# PowerStage.net
KiCad netlist of a schematic drawn in Altium Designer
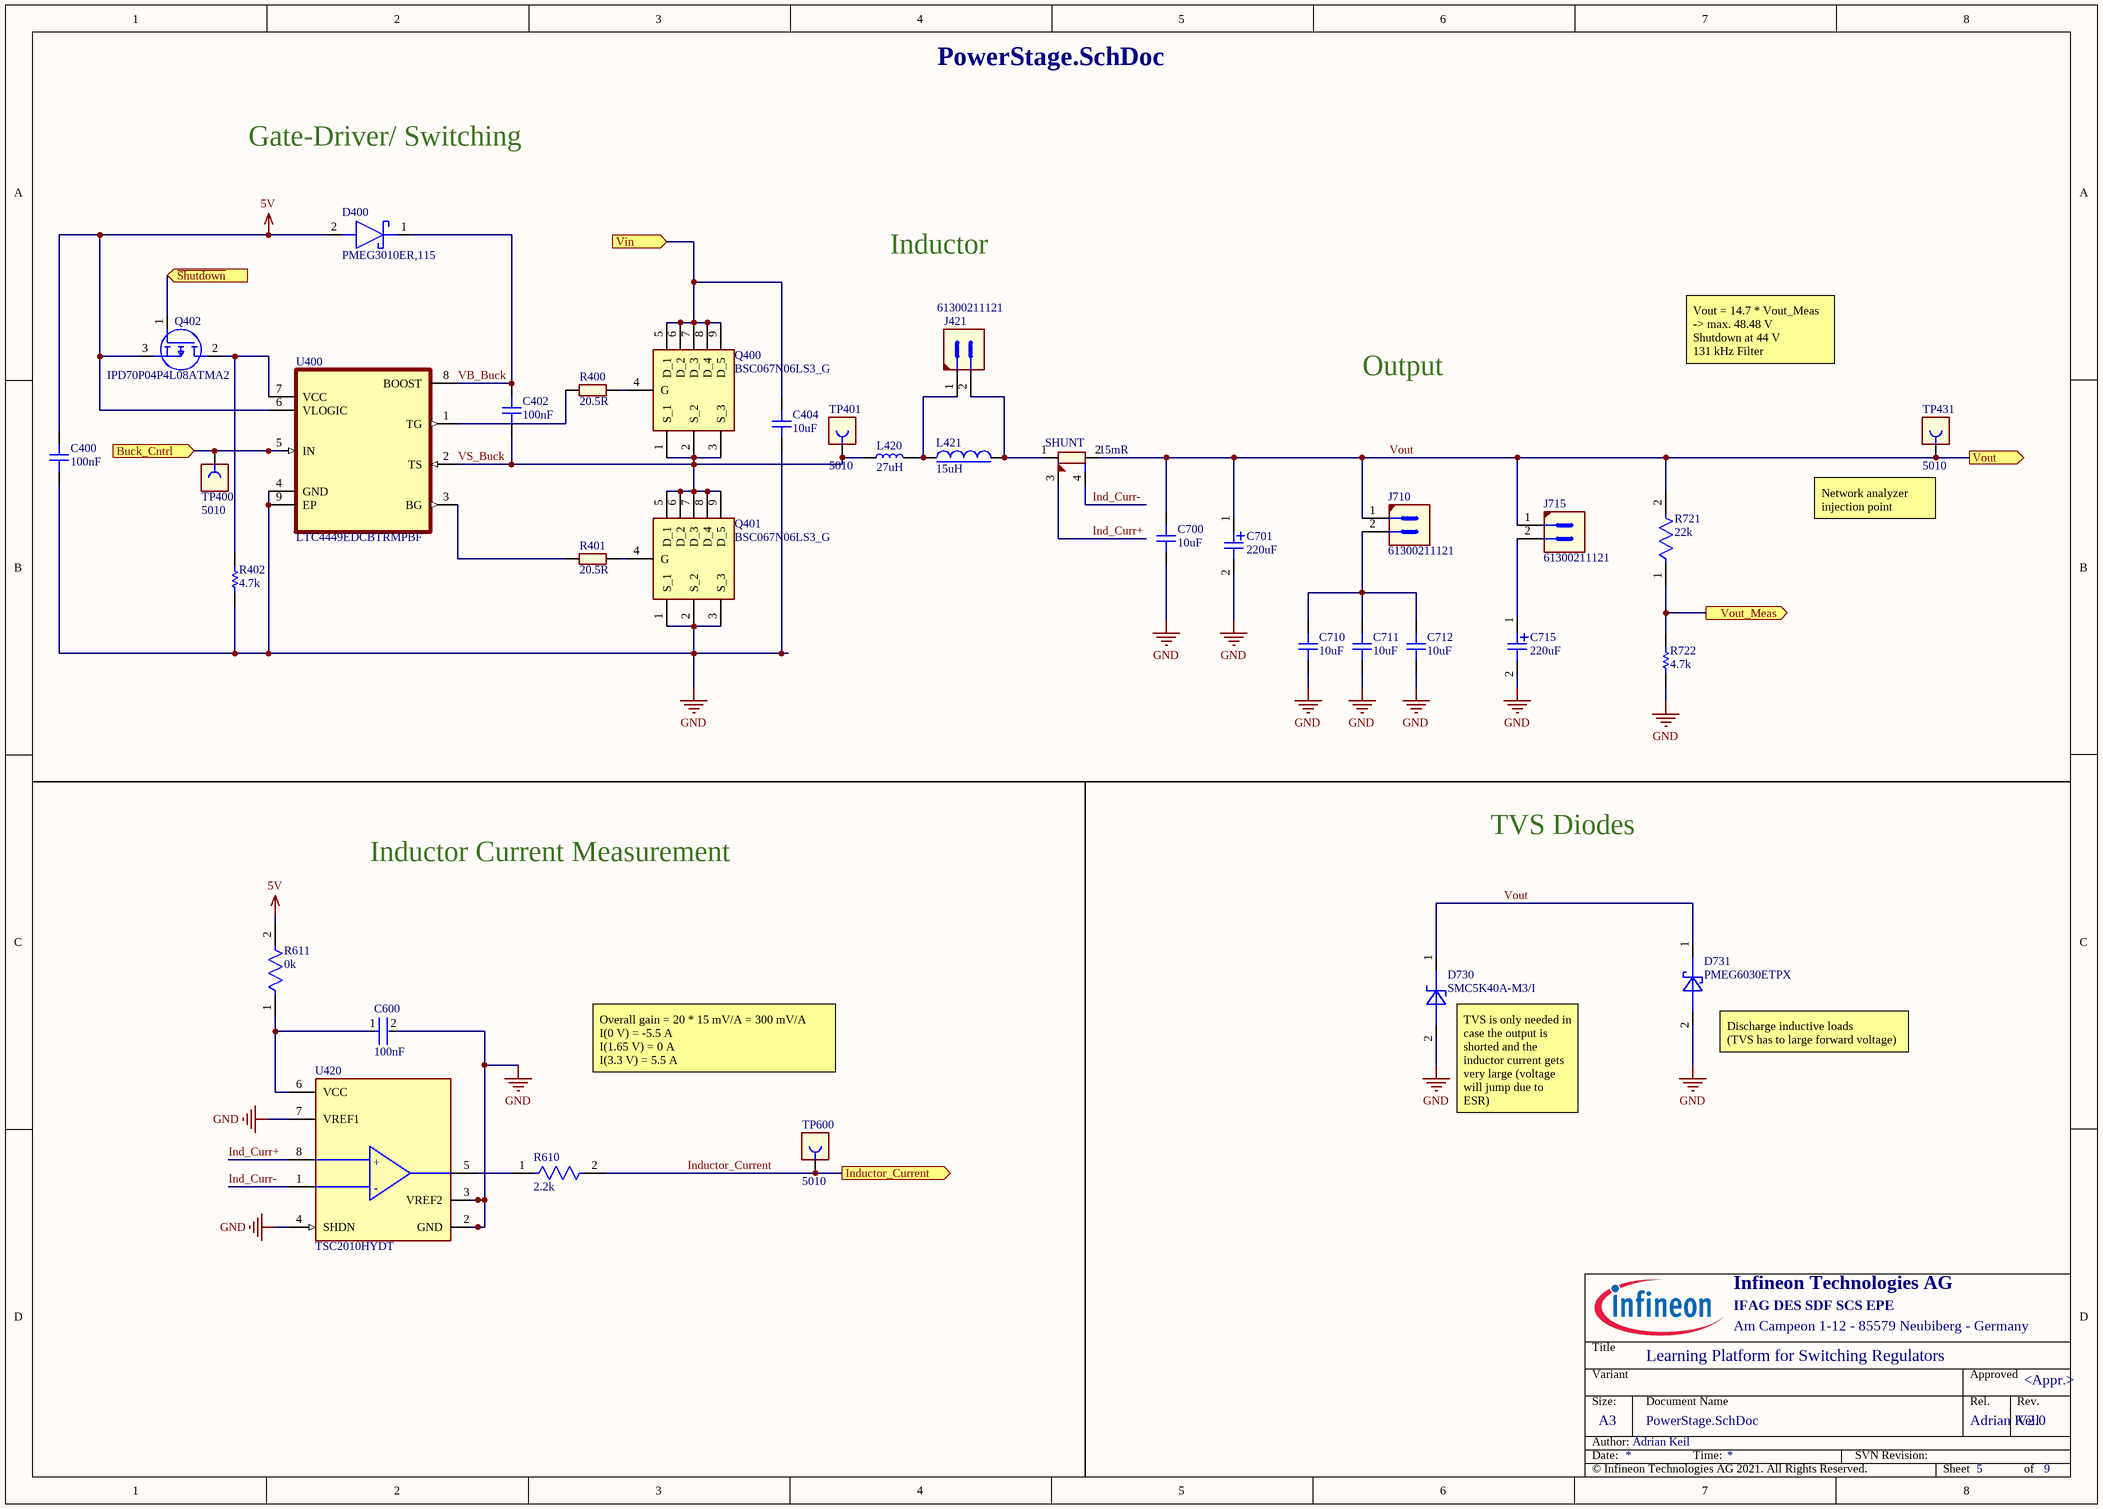
[diagram p0: PowerStage.SchDoc]

(export (version "E")
  (design (tool "Eeschema 10.0.6"))
  (components
    (comp (ref "C400")
      (value "100nF")
      (footprint "CAPC3216X125N-0")
      (description "CAP / CERA / 100nF / 50V / 10% / X7R (EIA) / -55°C to 125°C / 1206(3216) / SMD / -")
      (fields (field (name "LEGACY PARTNUMBER") "CAP01005660") (field (name "MANUFACTURER") "MuRata"))
      (libsource (lib "PCBLibraryData") (part "CAP-SGL-STD-02P_00000001"))
    )
    (comp (ref "C402")
      (value "100nF")
      (footprint "CAPC3216X125N-0")
      (description "CAP / CERA / 100nF / 50V / 10% / X7R (EIA) / -55°C to 125°C / 1206(3216) / SMD / -")
      (fields (field (name "LEGACY PARTNUMBER") "CAP01005660") (field (name "MANUFACTURER") "MuRata"))
      (libsource (lib "PCBLibraryData") (part "CAP-SGL-STD-02P_00000001"))
    )
    (comp (ref "C404")
      (value "10uF")
      (footprint "CAPC3216X190N-1")
      (description "CAP / CERA / 10uF / 50V / 20% / X5R (EIA) / -55°C to 85°C / 1206 (3216) / SMD / -")
      (fields (field (name "MANUFACTURER") "Taiyo Yuden"))
      (libsource (lib "PCBLibraryData") (part "CAP-SGL-STD-02P_00000001"))
    )
    (comp (ref "C600")
      (value "100nF")
      (footprint "FP-1206-L_3_2_0_2-W_1_6_0-MFG")
      (description "General Purpose Ceramic Capacitor, 1206, 100nF, 10%, X7R, 15%, 100V")
      (fields (field (name "TOLERANCE") "10%"))
      (libsource (lib "Altium Content Vault") (part "b4654b650e69147ec39a6b967a45e02"))
    )
    (comp (ref "C700")
      (value "10uF")
      (footprint "CAPC3216X190N-1")
      (description "CAP / CERA / 10uF / 50V / 20% / X5R (EIA) / -55°C to 85°C / 1206 (3216) / SMD / -")
      (fields (field (name "MANUFACTURER") "Taiyo Yuden"))
      (libsource (lib "PCBLibraryData") (part "CAP-SGL-STD-02P_00000001"))
    )
    (comp (ref "C701")
      (value "220uF")
      (footprint "CAPAE1030X1050N-3")
      (fields (field (name "MANUFACTURER") "Nippon Chemi-Con"))
      (libsource (lib "PCBLibraryData") (part "CAP-SGL-POL-02P_00000002"))
    )
    (comp (ref "C710")
      (value "10uF")
      (footprint "CAPC3216X190N-1")
      (description "CAP / CERA / 10uF / 50V / 20% / X5R (EIA) / -55°C to 85°C / 1206 (3216) / SMD / -")
      (fields (field (name "MANUFACTURER") "Taiyo Yuden") (field (name "LCSC PART #") "C97712"))
      (libsource (lib "PCBLibraryData") (part "CAP-SGL-STD-02P_00000001"))
    )
    (comp (ref "C711")
      (value "10uF")
      (footprint "CAPC3216X190N-1")
      (description "CAP / CERA / 10uF / 50V / 20% / X5R (EIA) / -55°C to 85°C / 1206 (3216) / SMD / -")
      (fields (field (name "MANUFACTURER") "Taiyo Yuden"))
      (libsource (lib "PCBLibraryData") (part "CAP-SGL-STD-02P_00000001"))
    )
    (comp (ref "C712")
      (value "10uF")
      (footprint "CAPC3216X190N-1")
      (description "CAP / CERA / 10uF / 50V / 20% / X5R (EIA) / -55°C to 85°C / 1206 (3216) / SMD / -")
      (fields (field (name "MANUFACTURER") "Taiyo Yuden"))
      (libsource (lib "PCBLibraryData") (part "CAP-SGL-STD-02P_00000001"))
    )
    (comp (ref "C715")
      (value "220uF")
      (footprint "CAPAE1030X1050N-3")
      (fields (field (name "MANUFACTURER") "Nippon Chemi-Con"))
      (libsource (lib "PCBLibraryData") (part "CAP-SGL-POL-02P_00000002"))
    )
    (comp (ref "D400")
      (value "PMEG3010ER,115")
      (footprint "myPcbLib:PMEG3010ER115")
      (description "Schottky Diode")
      (fields (field (name "MOUSER PART NUMBER") "771-PMEG3010ER115"))
      (libsource (lib "mySchlib") (part "PMEG3010ER,115"))
    )
    (comp (ref "D730")
      (value "SMC5K40A-M3/I")
      (footprint "DIOM7959X262N")
      (description "Surface Mount Transient Voltage Suppressors, Unidirectional, Very Fast Response Time")
      (fields (field (name "MANUFACTURER") "Vishay") (field (name "MPN") "5.0SMDJ40AS"))
      (libsource (lib "PCBLibraryData") (part "d_tvs_a"))
    )
    (comp (ref "D731")
      (value "PMEG6030ETPX")
      (footprint "SODFL4725X110N")
      (description "DIODE SCHOTTKY 60V 3A SOD128")
      (fields (field (name "MANUFACTURER") "Nexperia"))
      (libsource (lib "PCBLibraryData") (part "d_schottky_a"))
    )
    (comp (ref "J421")
      (value "61300211121")
      (footprint "CON-M-THT-61300211121")
      (description "Header, 2.54mm Pitch, 2 pin, Vertical, Single Row")
      (fields
        (field (name "LEGACY PARTNUMBER") "CON01500943")
        (field (name "MANUFACTURER") "Wurth Elektronik")
      )
      (libsource (lib "") (part "Header 2_1"))
    )
    (comp (ref "J710")
      (value "61300211121")
      (footprint "CON-M-THT-61300211121")
      (description "Header, 2.54mm Pitch, 2 pin, Vertical, Single Row")
      (fields
        (field (name "LEGACY PARTNUMBER") "CON01500943")
        (field (name "MANUFACTURER") "Wurth Elektronik")
      )
      (libsource (lib "PCBLibraryData") (part "Header 2"))
    )
    (comp (ref "J715")
      (value "61300211121")
      (footprint "CON-M-THT-61300211121")
      (description "Header, 2.54mm Pitch, 2 pin, Vertical, Single Row")
      (fields
        (field (name "LEGACY PARTNUMBER") "CON01500943")
        (field (name "MANUFACTURER") "Wurth Elektronik")
      )
      (libsource (lib "PCBLibraryData") (part "Header 2"))
    )
    (comp (ref "L420")
      (value "27uH")
      (footprint "INDM120120X1000N")
      (fields
        (field (name "MANUFACTURER") "Wurth Elektronik")
        (field (name "LCSC PART #") "C6404671")
        (field (name "MPN") "7447709270")
      )
      (libsource (lib "PCBLibraryData") (part "IND-SGL-STD-02P_00000015"))
    )
    (comp (ref "L421")
      (value "15uH")
      (footprint "IND-SMD-SRP6060FA")
      (fields
        (field (name "MANUFACTURER") "Bourns")
        (field (name "LCSC PART #") "C2047415")
        (field (name "MPN") "SRP6060FA-150M")
      )
      (libsource (lib "PCBLibraryData") (part "IND-SGL-STD-COR-02P_00000016"))
    )
    (comp (ref "Q400")
      (value "BSC067N06LS3_G")
      (footprint "myPcbLib:BSC080N03LSG")
      (description "MOSFET (N-Channel)")
      (fields
        (field (name "MANUFACTURER_PART_NUMBER") "BSC067N06LS3 G")
        (field (name "MOUSER PART NUMBER") "726-BSC067N06LS3G")
      )
      (libsource (lib "mySchlib") (part "BSC067N06LS3_G"))
    )
    (comp (ref "Q401")
      (value "BSC067N06LS3_G")
      (footprint "myPcbLib:BSC080N03LSG")
      (description "MOSFET (N-Channel)")
      (fields
        (field (name "MANUFACTURER_PART_NUMBER") "BSC067N06LS3 G")
        (field (name "MOUSER PART NUMBER") "726-BSC067N06LS3G")
      )
      (libsource (lib "mySchlib") (part "BSC067N06LS3_G"))
    )
    (comp (ref "Q402")
      (value "IPD70P04P4L08ATMA2")
      (footprint "myPcbLib:IPD70P04P4L08ATMA2")
      (description "MOSFET (P-Channel)")
      (fields (field (name "MOUSER PART NUMBER") "726-IPD70P04P4L08ATM"))
      (libsource (lib "mySchlib") (part "IPD70P04P4L08ATMA2"))
    )
    (comp (ref "R400")
      (value "20.5R")
      (footprint "RESC3216X60N")
      (description "RES / STD / 20.5R / 250mW / 1% / 100ppm/K / -55°C to 155°C / 1206(3216) / SMD / -")
      (fields (field (name "LEGACY PARTNUMBER") "RES01802548") (field (name "MANUFACTURER") "Vishay"))
      (libsource (lib "PCBLibraryData") (part "RES-SGL-STD-02P_00000006"))
    )
    (comp (ref "R401")
      (value "20.5R")
      (footprint "RESC3216X60N")
      (description "RES / STD / 20.5R / 250mW / 1% / 100ppm/K / -55°C to 155°C / 1206(3216) / SMD / -")
      (fields (field (name "LEGACY PARTNUMBER") "RES01802548") (field (name "MANUFACTURER") "Vishay"))
      (libsource (lib "PCBLibraryData") (part "RES-SGL-STD-02P_00000006"))
    )
    (comp (ref "R402")
      (value "4.7k")
      (footprint "RESC3216X60X45ML15T20")
      (description "Chip Resistor, 4.7 KOhm, +/- 1%, 0.25 W, -55 to 155 degC, 1206 (3216 Metric), RoHS, Tape and Reel")
      (fields (field (name "MANUFACTURER") "Vishay Semiconductor") (field (name "TOLERANCE") "1%"))
      (libsource (lib "Altium Content Vault") (part "RES-2"))
    )
    (comp (ref "R610")
      (value "2.2k")
      (footprint "FP-CRCW1206-e3-IPC_C")
      (description "RES Thick Film, 2.2kΩ, 1%, 0.25W, 100ppm/°C, 1206")
      (fields (field (name "TOLERANCE") "1%"))
      (libsource (lib "Altium Content Vault") (part "1029c3af85768c4190bb7ad29bc67b5"))
    )
    (comp (ref "R611")
      (value "0k")
      (footprint "FP-CRCW1206-e3-IPC_C")
      (description "RES Thick Film, 0Ω, 0.25W, 1206")
      (fields (field (name "TOLERANCE") "1%") (field (name "LCSC PART #") "C844861"))
      (libsource (lib "Altium Content Vault") (part "1029c3af85768c4190bb7ad29bc67b5"))
    )
    (comp (ref "R721")
      (value "22k")
      (footprint "FP-CRCW1206-e3-IPC_A")
      (description "RES Thick Film, 22kΩ, 1%, 0.25W, 100ppm/°C, 1206")
      (fields (field (name "TOLERANCE") "1%"))
      (libsource (lib "Altium Content Vault") (part "1029c3af85768c4190bb7ad29bc67b5"))
    )
    (comp (ref "R722")
      (value "4.7k")
      (footprint "RESC3216X60X45ML15T20")
      (description "Chip Resistor, 4.7 KOhm, +/- 1%, 0.25 W, -55 to 155 degC, 1206 (3216 Metric), RoHS, Tape and Reel")
      (fields (field (name "MANUFACTURER") "Vishay Semiconductor") (field (name "TOLERANCE") "1%"))
      (libsource (lib "Altium Content Vault") (part "RES-2"))
    )
    (comp (ref "SHUNT")
      (value "15mR")
      (footprint "RES-SMD-L4T12")
      (description "RES / STD / 15mR / 500mW / 1% / 75ppm/K / -55°C to 155°C / 1206 (3216) / SMD / -")
      (fields (field (name "MANUFACTURER") "Ohmite"))
      (libsource (lib "PCBLibraryData") (part "RES-SHT-STD-04P_00097BE5"))
    )
    (comp (ref "TP400")
      (value "5010")
      (footprint "CON-THT-TP-5010")
      (description "PC Test Point-Multipurpose THT, Red")
      (fields
        (field (name "LEGACY PARTNUMBER") "CON01500529")
        (field (name "MANUFACTURER") "Keystone Electronics Corp.")
      )
      (libsource (lib "") (part "connector_1_f_1"))
    )
    (comp (ref "TP401")
      (value "5010")
      (footprint "CON-THT-TP-5010")
      (description "PC Test Point-Multipurpose THT, Red")
      (fields
        (field (name "LEGACY PARTNUMBER") "CON01500529")
        (field (name "MANUFACTURER") "Keystone Electronics Corp.")
      )
      (libsource (lib "PCBLibraryData") (part "connector_1_f"))
    )
    (comp (ref "TP431")
      (value "5010")
      (footprint "CON-THT-TP-5010")
      (description "PC Test Point-Multipurpose THT, Red")
      (fields
        (field (name "LEGACY PARTNUMBER") "CON01500529")
        (field (name "MANUFACTURER") "Keystone Electronics Corp.")
      )
      (libsource (lib "PCBLibraryData") (part "connector_1_f"))
    )
    (comp (ref "TP600")
      (value "5010")
      (footprint "CON-THT-TP-5010")
      (description "PC Test Point-Multipurpose THT, Red")
      (fields
        (field (name "LEGACY PARTNUMBER") "CON01500529")
        (field (name "MANUFACTURER") "Keystone Electronics Corp.")
      )
      (libsource (lib "PCBLibraryData") (part "connector_1_f"))
    )
    (comp (ref "U400")
      (value "LTC4449EDCBTRMPBF")
      (footprint "DFN200X300X80-9N")
      (description "High Speed Synchronous N-Channel MOSFET Driver")
      (fields (field (name "LCSC PART #") "C580913") (field (name "MPN") "LTC4449EDCB#TRMPBF"))
      (libsource (lib "mySchlib") (part "LTC4449EDCBTRMPBF"))
    )
    (comp (ref "U420")
      (value "TSC2010HYDT")
      (footprint "FP-SO8-IPC_C")
      (description "IC CURRENT SENSE 1 CIRCUIT 8SOIC")
      (fields (field (name "LCSC PART #") "C4370994"))
      (libsource (lib "Altium Content Vault") (part "148e0707e4e6d103058ae51fa0bcede"))
    )
  )
  (nets
    (net (code "1") (name "/Buck_Cntrl") (class "Default")
      (node (ref "TP400") (pin "1") (pinfunction "1_1") (pintype "passive"))
      (node (ref "U400") (pin "5") (pinfunction "IN_5") (pintype "input"))
    )
    (net (code "2") (name "/Ind_Curr+") (class "Default")
      (node (ref "SHUNT") (pin "3") (pinfunction "I1_3") (pintype "passive"))
      (node (ref "U420") (pin "8") (pinfunction "IN+_8") (pintype "tri_state"))
    )
    (net (code "3") (name "/Ind_Curr-") (class "Default")
      (node (ref "SHUNT") (pin "4") (pinfunction "I2_4") (pintype "passive"))
      (node (ref "U420") (pin "1") (pinfunction "IN-_1") (pintype "tri_state"))
    )
    (net (code "4") (name "/Inductor_Current") (class "Default")
      (node (ref "R610") (pin "2") (pinfunction "2_2") (pintype "passive"))
      (node (ref "TP600") (pin "1") (pinfunction "1_1") (pintype "passive"))
    )
    (net (code "5") (name "/Shutdown") (class "Default")
      (node (ref "Q402") (pin "1") (pinfunction "G_1") (pintype "passive"))
    )
    (net (code "6") (name "/VB_Buck") (class "Default")
      (node (ref "C402") (pin "2") (pinfunction "2_2") (pintype "passive"))
      (node (ref "D400") (pin "1") (pinfunction "K_1") (pintype "passive"))
      (node (ref "U400") (pin "8") (pinfunction "BOOST_8") (pintype "power_in"))
    )
    (net (code "7") (name "/VS_Buck") (class "Default")
      (node (ref "C402") (pin "1") (pinfunction "1_1") (pintype "passive"))
      (node (ref "L420") (pin "1") (pinfunction "1_1") (pintype "passive"))
      (node (ref "Q400") (pin "1") (pinfunction "S_1_1") (pintype "passive"))
      (node (ref "Q400") (pin "2") (pinfunction "S_2_2") (pintype "passive"))
      (node (ref "Q400") (pin "3") (pinfunction "S_3_3") (pintype "passive"))
      (node (ref "Q401") (pin "5") (pinfunction "D_1_5") (pintype "passive"))
      (node (ref "Q401") (pin "6") (pinfunction "D_2_6") (pintype "passive"))
      (node (ref "Q401") (pin "7") (pinfunction "D_3_7") (pintype "passive"))
      (node (ref "Q401") (pin "8") (pinfunction "D_4_8") (pintype "passive"))
      (node (ref "Q401") (pin "9") (pinfunction "D_5_9") (pintype "passive"))
      (node (ref "TP401") (pin "1") (pinfunction "1_1") (pintype "passive"))
      (node (ref "U400") (pin "2") (pinfunction "TS_2") (pintype "input"))
    )
    (net (code "8") (name "/Vin") (class "Default")
      (node (ref "C404") (pin "2") (pinfunction "2_2") (pintype "passive"))
      (node (ref "Q400") (pin "5") (pinfunction "D_1_5") (pintype "passive"))
      (node (ref "Q400") (pin "6") (pinfunction "D_2_6") (pintype "passive"))
      (node (ref "Q400") (pin "7") (pinfunction "D_3_7") (pintype "passive"))
      (node (ref "Q400") (pin "8") (pinfunction "D_4_8") (pintype "passive"))
      (node (ref "Q400") (pin "9") (pinfunction "D_5_9") (pintype "passive"))
    )
    (net (code "9") (name "/Vout") (class "Default")
      (node (ref "C700") (pin "2") (pinfunction "2_2") (pintype "passive"))
      (node (ref "C701") (pin "1") (pinfunction "1_1") (pintype "passive"))
      (node (ref "D730") (pin "1") (pinfunction "CATHODE_1") (pintype "passive"))
      (node (ref "D731") (pin "1") (pinfunction "Cathode_1") (pintype "passive"))
      (node (ref "J710") (pin "1") (pinfunction "1_1") (pintype "passive"))
      (node (ref "J715") (pin "1") (pinfunction "1_1") (pintype "passive"))
      (node (ref "R721") (pin "2") (pinfunction "2_2") (pintype "passive"))
      (node (ref "SHUNT") (pin "2") (pinfunction "V2_2") (pintype "passive"))
      (node (ref "TP431") (pin "1") (pinfunction "1_1") (pintype "passive"))
    )
    (net (code "10") (name "/Vout_Meas") (class "Default")
      (node (ref "R721") (pin "1") (pinfunction "1_1") (pintype "passive"))
      (node (ref "R722") (pin "2") (pinfunction "2_2") (pintype "passive"))
    )
    (net (code "11") (name "5V") (class "Default")
      (node (ref "C400") (pin "2") (pinfunction "2_2") (pintype "passive"))
      (node (ref "D400") (pin "2") (pinfunction "A_2") (pintype "passive"))
      (node (ref "Q402") (pin "3") (pinfunction "S_3") (pintype "passive"))
      (node (ref "R611") (pin "2") (pinfunction "2_2") (pintype "passive"))
      (node (ref "U400") (pin "6") (pinfunction "VLOGIC_6") (pintype "power_in"))
    )
    (net (code "12") (name "GND") (class "Default")
      (node (ref "C400") (pin "1") (pinfunction "1_1") (pintype "passive"))
      (node (ref "C404") (pin "1") (pinfunction "1_1") (pintype "passive"))
      (node (ref "C600") (pin "2") (pinfunction "2_2") (pintype "passive"))
      (node (ref "C700") (pin "1") (pinfunction "1_1") (pintype "passive"))
      (node (ref "C701") (pin "2") (pinfunction "2_2") (pintype "passive"))
      (node (ref "C710") (pin "1") (pinfunction "1_1") (pintype "passive"))
      (node (ref "C711") (pin "1") (pinfunction "1_1") (pintype "passive"))
      (node (ref "C712") (pin "1") (pinfunction "1_1") (pintype "passive"))
      (node (ref "C715") (pin "2") (pinfunction "2_2") (pintype "passive"))
      (node (ref "D730") (pin "2") (pinfunction "ANODE_2") (pintype "passive"))
      (node (ref "D731") (pin "2") (pinfunction "Anode_2") (pintype "passive"))
      (node (ref "Q401") (pin "1") (pinfunction "S_1_1") (pintype "passive"))
      (node (ref "Q401") (pin "2") (pinfunction "S_2_2") (pintype "passive"))
      (node (ref "Q401") (pin "3") (pinfunction "S_3_3") (pintype "passive"))
      (node (ref "R402") (pin "1") (pinfunction "1_1") (pintype "passive"))
      (node (ref "R722") (pin "1") (pinfunction "1_1") (pintype "passive"))
      (node (ref "U400") (pin "4") (pinfunction "GND_4") (pintype "passive"))
      (node (ref "U400") (pin "9") (pinfunction "EP_9") (pintype "passive"))
      (node (ref "U420") (pin "2") (pinfunction "GND_2") (pintype "power_in"))
      (node (ref "U420") (pin "3") (pinfunction "VREF2_3") (pintype "passive"))
      (node (ref "U420") (pin "4") (pinfunction "SHDN_4") (pintype "input"))
      (node (ref "U420") (pin "7") (pinfunction "VREF1_7") (pintype "passive"))
    )
    (net (code "13") (name "Net-(C710-Pad2)") (class "Default")
      (node (ref "C710") (pin "2") (pinfunction "2_2") (pintype "passive"))
      (node (ref "C711") (pin "2") (pinfunction "2_2") (pintype "passive"))
      (node (ref "C712") (pin "2") (pinfunction "2_2") (pintype "passive"))
      (node (ref "J710") (pin "2") (pinfunction "2_2") (pintype "passive"))
    )
    (net (code "14") (name "Net-(C715-Pad1)") (class "Default")
      (node (ref "C715") (pin "1") (pinfunction "1_1") (pintype "passive"))
      (node (ref "J715") (pin "2") (pinfunction "2_2") (pintype "passive"))
    )
    (net (code "15") (name "Net-(J421-Pad1)") (class "Default")
      (node (ref "J421") (pin "1") (pinfunction "1_1") (pintype "passive"))
      (node (ref "L420") (pin "2") (pinfunction "2_2") (pintype "passive"))
      (node (ref "L421") (pin "1") (pinfunction "1_1") (pintype "passive"))
    )
    (net (code "16") (name "Net-(Q400-G)") (class "Default")
      (node (ref "Q400") (pin "4") (pinfunction "G_4") (pintype "passive"))
      (node (ref "R400") (pin "1") (pinfunction "1_1") (pintype "passive"))
    )
    (net (code "17") (name "Net-(Q401-G)") (class "Default")
      (node (ref "Q401") (pin "4") (pinfunction "G_4") (pintype "passive"))
      (node (ref "R401") (pin "1") (pinfunction "1_1") (pintype "passive"))
    )
    (net (code "18") (name "Net-(Q402-D)") (class "Default")
      (node (ref "Q402") (pin "2") (pinfunction "D_2") (pintype "passive"))
      (node (ref "R402") (pin "2") (pinfunction "2_2") (pintype "passive"))
      (node (ref "U400") (pin "7") (pinfunction "VCC_7") (pintype "power_in"))
    )
    (net (code "19") (name "Net-(SHUNT-V1)") (class "Default")
      (node (ref "J421") (pin "2") (pinfunction "2_2") (pintype "passive"))
      (node (ref "L421") (pin "2") (pinfunction "2_2") (pintype "passive"))
      (node (ref "SHUNT") (pin "1") (pinfunction "V1_1") (pintype "passive"))
    )
    (net (code "20") (name "Net-(U400-BG)") (class "Default")
      (node (ref "R401") (pin "2") (pinfunction "2_2") (pintype "passive"))
      (node (ref "U400") (pin "3") (pinfunction "BG_3") (pintype "output"))
    )
    (net (code "21") (name "Net-(U400-TG)") (class "Default")
      (node (ref "R400") (pin "2") (pinfunction "2_2") (pintype "passive"))
      (node (ref "U400") (pin "1") (pinfunction "TG_1") (pintype "output"))
    )
    (net (code "22") (name "Net-(U420-OUT)") (class "Default")
      (node (ref "R610") (pin "1") (pinfunction "1_1") (pintype "passive"))
      (node (ref "U420") (pin "5") (pinfunction "OUT_5") (pintype "passive"))
    )
    (net (code "23") (name "Net-(U420-VCC)") (class "Default")
      (node (ref "C600") (pin "1") (pinfunction "1_1") (pintype "passive"))
      (node (ref "R611") (pin "1") (pinfunction "1_1") (pintype "passive"))
      (node (ref "U420") (pin "6") (pinfunction "VCC_6") (pintype "power_in"))
    )
  )
)
